# Sheet1.net
KiCad netlist of a schematic drawn in Altium Designer
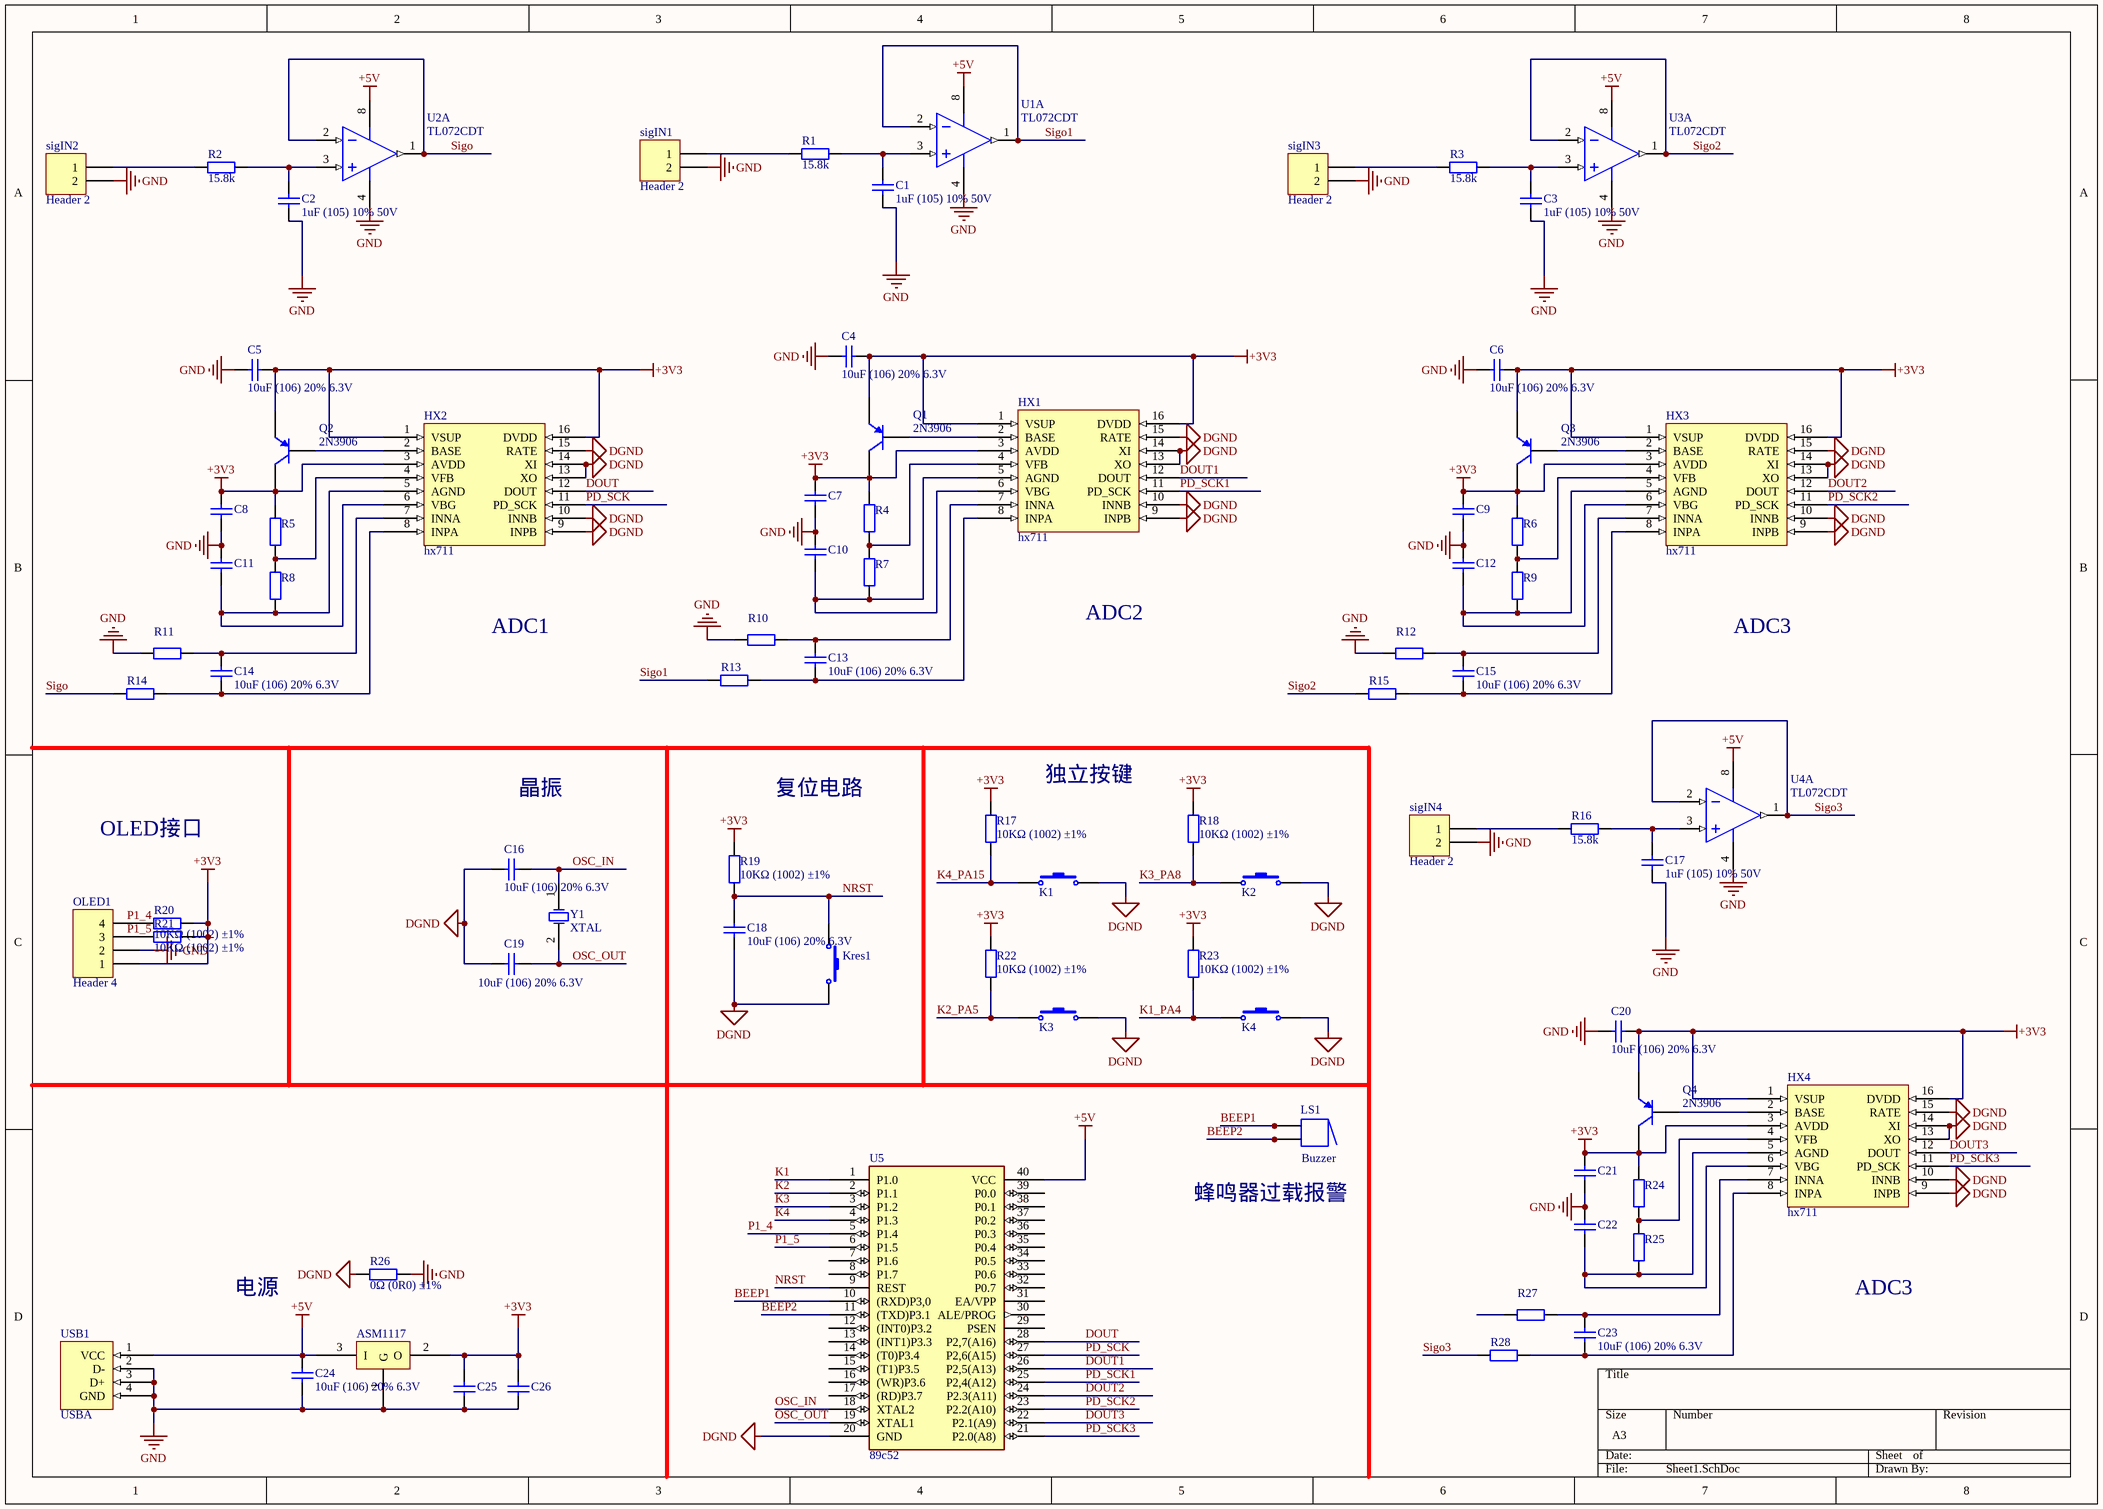
[diagram p0: Sheet1.SchDoc]

(export (version "E")
  (design (tool "Eeschema 10.0.6"))
  (components
    (comp (ref "asm1") (value "ASM1117") (footprint "1117PCB") (libsource (lib "AD603") (part "1117")))
    (comp (ref "C1")
      (value "1uF (105) 10% 50V")
      (footprint "0805_C")
      (description "贴片电容")
      (libsource (lib "Miscellaneous Devices LC") (part "0805 1uF (105) 10% 50V"))
    )
    (comp (ref "C2")
      (value "1uF (105) 10% 50V")
      (footprint "0805_C")
      (description "贴片电容")
      (libsource (lib "Miscellaneous Devices LC") (part "0805 1uF (105) 10% 50V"))
    )
    (comp (ref "C3")
      (value "1uF (105) 10% 50V")
      (footprint "0805_C")
      (description "贴片电容")
      (libsource (lib "Miscellaneous Devices LC") (part "0805 1uF (105) 10% 50V"))
    )
    (comp (ref "C4")
      (value "10uF (106) 20% 6.3V")
      (footprint "0402_C")
      (description "贴片电容")
      (libsource (lib "Miscellaneous Devices LC") (part "0402 10uF (106) 20% 6.3V"))
    )
    (comp (ref "C5")
      (value "10uF (106) 20% 6.3V")
      (footprint "0402_C")
      (description "贴片电容")
      (libsource (lib "Miscellaneous Devices LC") (part "0402 10uF (106) 20% 6.3V"))
    )
    (comp (ref "C6")
      (value "10uF (106) 20% 6.3V")
      (footprint "0402_C")
      (description "贴片电容")
      (libsource (lib "Miscellaneous Devices LC") (part "0402 10uF (106) 20% 6.3V"))
    )
    (comp (ref "C7")
      (value "10uF (106) 20% 6.3V")
      (footprint "0402_C")
      (description "贴片电容")
      (libsource (lib "Miscellaneous Devices LC") (part "0402 10uF (106) 20% 6.3V"))
    )
    (comp (ref "C8")
      (value "10uF (106) 20% 6.3V")
      (footprint "0402_C")
      (description "贴片电容")
      (libsource (lib "Miscellaneous Devices LC") (part "0402 10uF (106) 20% 6.3V"))
    )
    (comp (ref "C9")
      (value "10uF (106) 20% 6.3V")
      (footprint "0402_C")
      (description "贴片电容")
      (libsource (lib "Miscellaneous Devices LC") (part "0402 10uF (106) 20% 6.3V"))
    )
    (comp (ref "C10")
      (value "10uF (106) 20% 6.3V")
      (footprint "0402_C")
      (description "贴片电容")
      (libsource (lib "Miscellaneous Devices LC") (part "0402 10uF (106) 20% 6.3V"))
    )
    (comp (ref "C11")
      (value "10uF (106) 20% 6.3V")
      (footprint "0402_C")
      (description "贴片电容")
      (libsource (lib "Miscellaneous Devices LC") (part "0402 10uF (106) 20% 6.3V"))
    )
    (comp (ref "C12")
      (value "10uF (106) 20% 6.3V")
      (footprint "0402_C")
      (description "贴片电容")
      (libsource (lib "Miscellaneous Devices LC") (part "0402 10uF (106) 20% 6.3V"))
    )
    (comp (ref "C13")
      (value "10uF (106) 20% 6.3V")
      (footprint "0402_C")
      (description "贴片电容")
      (libsource (lib "Miscellaneous Devices LC") (part "0402 10uF (106) 20% 6.3V"))
    )
    (comp (ref "C14")
      (value "10uF (106) 20% 6.3V")
      (footprint "0402_C")
      (description "贴片电容")
      (libsource (lib "Miscellaneous Devices LC") (part "0402 10uF (106) 20% 6.3V"))
    )
    (comp (ref "C15")
      (value "10uF (106) 20% 6.3V")
      (footprint "0402_C")
      (description "贴片电容")
      (libsource (lib "Miscellaneous Devices LC") (part "0402 10uF (106) 20% 6.3V"))
    )
    (comp (ref "C16")
      (value "10uF (106) 20% 6.3V")
      (footprint "0402_C")
      (description "贴片电容")
      (libsource (lib "Miscellaneous Devices LC") (part "0402 10uF (106) 20% 6.3V"))
    )
    (comp (ref "C17")
      (value "1uF (105) 10% 50V")
      (footprint "0805_C")
      (description "贴片电容")
      (libsource (lib "Miscellaneous Devices LC") (part "0805 1uF (105) 10% 50V"))
    )
    (comp (ref "C18")
      (value "10uF (106) 20% 6.3V")
      (footprint "0402_C")
      (description "贴片电容")
      (libsource (lib "Miscellaneous Devices LC") (part "0402 10uF (106) 20% 6.3V"))
    )
    (comp (ref "C19")
      (value "10uF (106) 20% 6.3V")
      (footprint "0402_C")
      (description "贴片电容")
      (libsource (lib "Miscellaneous Devices LC") (part "0402 10uF (106) 20% 6.3V"))
    )
    (comp (ref "C20")
      (value "10uF (106) 20% 6.3V")
      (footprint "0402_C")
      (description "贴片电容")
      (libsource (lib "Miscellaneous Devices LC") (part "0402 10uF (106) 20% 6.3V"))
    )
    (comp (ref "C21")
      (value "10uF (106) 20% 6.3V")
      (footprint "0402_C")
      (description "贴片电容")
      (libsource (lib "Miscellaneous Devices LC") (part "0402 10uF (106) 20% 6.3V"))
    )
    (comp (ref "C22")
      (value "10uF (106) 20% 6.3V")
      (footprint "0402_C")
      (description "贴片电容")
      (libsource (lib "Miscellaneous Devices LC") (part "0402 10uF (106) 20% 6.3V"))
    )
    (comp (ref "C23")
      (value "10uF (106) 20% 6.3V")
      (footprint "0402_C")
      (description "贴片电容")
      (libsource (lib "Miscellaneous Devices LC") (part "0402 10uF (106) 20% 6.3V"))
    )
    (comp (ref "C24")
      (value "10uF (106) 20% 6.3V")
      (footprint "0402_C")
      (description "贴片电容")
      (libsource (lib "Miscellaneous Devices LC") (part "0402 10uF (106) 20% 6.3V"))
    )
    (comp (ref "C25")
      (value "10uF (106) 20% 6.3V")
      (footprint "0402_C")
      (description "贴片电容")
      (libsource (lib "Miscellaneous Devices LC") (part "0402 10uF (106) 20% 6.3V"))
    )
    (comp (ref "C26")
      (value "10uF (106) 20% 6.3V")
      (footprint "0402_C")
      (description "贴片电容")
      (libsource (lib "Miscellaneous Devices LC") (part "0402 10uF (106) 20% 6.3V"))
    )
    (comp (ref "HX1") (value "hx711") (footprint "HX711") (libsource (lib "Schlib1") (part "hx711")))
    (comp (ref "HX2") (value "hx711") (footprint "HX711") (libsource (lib "Schlib1") (part "hx711")))
    (comp (ref "HX3") (value "hx711") (footprint "HX711") (libsource (lib "Schlib1") (part "hx711")))
    (comp (ref "HX4") (value "hx711") (footprint "HX711") (libsource (lib "Schlib1") (part "hx711")))
    (comp (ref "K1") (value "key") (footprint "KEYPCB") (libsource (lib "zhj's footprint") (part "key")))
    (comp (ref "K2") (value "key") (footprint "KEYPCB") (libsource (lib "zhj's footprint") (part "key")))
    (comp (ref "K3") (value "key") (footprint "KEYPCB") (libsource (lib "zhj's footprint") (part "key")))
    (comp (ref "K4") (value "key") (footprint "KEYPCB") (libsource (lib "zhj's footprint") (part "key")))
    (comp (ref "Kres1") (value "key") (footprint "KEYPCB") (libsource (lib "zhj's footprint") (part "key")))
    (comp (ref "LS1")
      (value "Buzzer")
      (footprint "ABSM-1574")
      (description "Magnetic Transducer Buzzer")
      (fields (field (name "PUBLISHER") "Altium Limited"))
      (libsource (lib "Miscellaneous Devices") (part "Buzzer"))
    )
    (comp (ref "OLED1")
      (value "Header 4")
      (footprint "HDR1X4")
      (description "Header, 4-Pin")
      (fields (field (name "PUBLISHER") "Altium Limited"))
      (libsource (lib "Miscellaneous Connectors") (part "Header 4"))
    )
    (comp (ref "Q1")
      (value "2N3906")
      (footprint "TO-92A")
      (description "PNP General Purpose Amplifier")
      (fields (field (name "PUBLISHER") "Altium Limited"))
      (libsource (lib "Miscellaneous Devices") (part "2N3906"))
    )
    (comp (ref "Q2")
      (value "2N3906")
      (footprint "TO-92A")
      (description "PNP General Purpose Amplifier")
      (fields (field (name "PUBLISHER") "Altium Limited"))
      (libsource (lib "Miscellaneous Devices") (part "2N3906"))
    )
    (comp (ref "Q3")
      (value "2N3906")
      (footprint "TO-92A")
      (description "PNP General Purpose Amplifier")
      (fields (field (name "PUBLISHER") "Altium Limited"))
      (libsource (lib "Miscellaneous Devices") (part "2N3906"))
    )
    (comp (ref "Q4")
      (value "2N3906")
      (footprint "TO-92A")
      (description "PNP General Purpose Amplifier")
      (fields (field (name "PUBLISHER") "Altium Limited"))
      (libsource (lib "Miscellaneous Devices") (part "2N3906"))
    )
    (comp (ref "R1")
      (value "15.8k")
      (footprint "0805_R")
      (description "贴片电阻")
      (libsource (lib "Miscellaneous Devices LC") (part "0805 330KΩ (3303) 1%"))
    )
    (comp (ref "R2")
      (value "15.8k")
      (footprint "0805_R")
      (description "贴片电阻")
      (libsource (lib "Miscellaneous Devices LC") (part "0805 330KΩ (3303) 1%"))
    )
    (comp (ref "R3")
      (value "15.8k")
      (footprint "0805_R")
      (description "贴片电阻")
      (libsource (lib "Miscellaneous Devices LC") (part "0805 330KΩ (3303) 1%"))
    )
    (comp (ref "R4")
      (value "10KΩ (1002) ±1%")
      (footprint "0603_R")
      (description "贴片电阻")
      (libsource (lib "Miscellaneous Devices LC") (part "0603 10KΩ (1002) 1%"))
    )
    (comp (ref "R5")
      (value "10KΩ (1002) ±1%")
      (footprint "0603_R")
      (description "贴片电阻")
      (libsource (lib "Miscellaneous Devices LC") (part "0603 10KΩ (1002) 1%"))
    )
    (comp (ref "R6")
      (value "10KΩ (1002) ±1%")
      (footprint "0603_R")
      (description "贴片电阻")
      (libsource (lib "Miscellaneous Devices LC") (part "0603 10KΩ (1002) 1%"))
    )
    (comp (ref "R7")
      (value "10KΩ (1002) ±1%")
      (footprint "0603_R")
      (description "贴片电阻")
      (libsource (lib "Miscellaneous Devices LC") (part "0603 10KΩ (1002) 1%"))
    )
    (comp (ref "R8")
      (value "10KΩ (1002) ±1%")
      (footprint "0603_R")
      (description "贴片电阻")
      (libsource (lib "Miscellaneous Devices LC") (part "0603 10KΩ (1002) 1%"))
    )
    (comp (ref "R9")
      (value "10KΩ (1002) ±1%")
      (footprint "0603_R")
      (description "贴片电阻")
      (libsource (lib "Miscellaneous Devices LC") (part "0603 10KΩ (1002) 1%"))
    )
    (comp (ref "R10")
      (value "1KΩ (1002) ±1%")
      (footprint "0603_R")
      (description "贴片电阻")
      (libsource (lib "") (part "0603 10KΩ (1002) 1%_1"))
    )
    (comp (ref "R11")
      (value "1KΩ (1002) ±1%")
      (footprint "0603_R")
      (description "贴片电阻")
      (libsource (lib "") (part "0603 10KΩ (1002) 1%_1"))
    )
    (comp (ref "R12")
      (value "1KΩ (1002) ±1%")
      (footprint "0603_R")
      (description "贴片电阻")
      (libsource (lib "") (part "0603 10KΩ (1002) 1%_1"))
    )
    (comp (ref "R13")
      (value "1KΩ (1002) ±1%")
      (footprint "0603_R")
      (description "贴片电阻")
      (libsource (lib "") (part "0603 10KΩ (1002) 1%_1"))
    )
    (comp (ref "R14")
      (value "1KΩ (1002) ±1%")
      (footprint "0603_R")
      (description "贴片电阻")
      (libsource (lib "") (part "0603 10KΩ (1002) 1%_1"))
    )
    (comp (ref "R15")
      (value "1KΩ (1002) ±1%")
      (footprint "0603_R")
      (description "贴片电阻")
      (libsource (lib "") (part "0603 10KΩ (1002) 1%_1"))
    )
    (comp (ref "R16")
      (value "15.8k")
      (footprint "0805_R")
      (description "贴片电阻")
      (libsource (lib "Miscellaneous Devices LC") (part "0805 330KΩ (3303) 1%"))
    )
    (comp (ref "R17")
      (value "10KΩ (1002) ±1%")
      (footprint "0603_R")
      (description "贴片电阻")
      (libsource (lib "Miscellaneous Devices LC") (part "0603 10KΩ (1002) 1%"))
    )
    (comp (ref "R18")
      (value "10KΩ (1002) ±1%")
      (footprint "0603_R")
      (description "贴片电阻")
      (libsource (lib "Miscellaneous Devices LC") (part "0603 10KΩ (1002) 1%"))
    )
    (comp (ref "R19")
      (value "10KΩ (1002) ±1%")
      (footprint "0603_R")
      (description "贴片电阻")
      (libsource (lib "Miscellaneous Devices LC") (part "0603 10KΩ (1002) 1%"))
    )
    (comp (ref "R20")
      (value "10KΩ (1002) ±1%")
      (footprint "0603_R")
      (description "贴片电阻")
      (libsource (lib "") (part "0603 10KΩ (1002) 1%_1"))
    )
    (comp (ref "R21")
      (value "10KΩ (1002) ±1%")
      (footprint "0603_R")
      (description "贴片电阻")
      (libsource (lib "") (part "0603 10KΩ (1002) 1%_1"))
    )
    (comp (ref "R22")
      (value "10KΩ (1002) ±1%")
      (footprint "0603_R")
      (description "贴片电阻")
      (libsource (lib "Miscellaneous Devices LC") (part "0603 10KΩ (1002) 1%"))
    )
    (comp (ref "R23")
      (value "10KΩ (1002) ±1%")
      (footprint "0603_R")
      (description "贴片电阻")
      (libsource (lib "Miscellaneous Devices LC") (part "0603 10KΩ (1002) 1%"))
    )
    (comp (ref "R24")
      (value "10KΩ (1002) ±1%")
      (footprint "0603_R")
      (description "贴片电阻")
      (libsource (lib "Miscellaneous Devices LC") (part "0603 10KΩ (1002) 1%"))
    )
    (comp (ref "R25")
      (value "10KΩ (1002) ±1%")
      (footprint "0603_R")
      (description "贴片电阻")
      (libsource (lib "Miscellaneous Devices LC") (part "0603 10KΩ (1002) 1%"))
    )
    (comp (ref "R26")
      (value "0Ω (0R0) ±1%")
      (footprint "0603_R")
      (description "贴片电阻")
      (libsource (lib "Miscellaneous Devices LC") (part "0603 0Ω (0R0) 1%"))
    )
    (comp (ref "R27")
      (value "1KΩ (1002) ±1%")
      (footprint "0603_R")
      (description "贴片电阻")
      (libsource (lib "") (part "0603 10KΩ (1002) 1%_1"))
    )
    (comp (ref "R28")
      (value "1KΩ (1002) ±1%")
      (footprint "0603_R")
      (description "贴片电阻")
      (libsource (lib "") (part "0603 10KΩ (1002) 1%_1"))
    )
    (comp (ref "sigIN1")
      (value "Header 2")
      (footprint "HDR1X2")
      (description "Header, 2-Pin")
      (fields (field (name "PUBLISHER") "Altium Limited"))
      (libsource (lib "Miscellaneous Connectors") (part "Header 2"))
    )
    (comp (ref "sigIN2")
      (value "Header 2")
      (footprint "HDR1X2")
      (description "Header, 2-Pin")
      (fields (field (name "PUBLISHER") "Altium Limited"))
      (libsource (lib "Miscellaneous Connectors") (part "Header 2"))
    )
    (comp (ref "sigIN3")
      (value "Header 2")
      (footprint "HDR1X2")
      (description "Header, 2-Pin")
      (fields (field (name "PUBLISHER") "Altium Limited"))
      (libsource (lib "Miscellaneous Connectors") (part "Header 2"))
    )
    (comp (ref "sigIN4")
      (value "Header 2")
      (footprint "HDR1X2")
      (description "Header, 2-Pin")
      (fields (field (name "PUBLISHER") "Altium Limited"))
      (libsource (lib "Miscellaneous Connectors") (part "Header 2"))
    )
    (comp (ref "U1")
      (value "TL072CDT")
      (footprint "SOIC-8_150mil")
      (description "运放")
      (libsource (lib "Miscellaneous Devices LC") (part "TL072CDT_[C6961]"))
    )
    (comp (ref "U2")
      (value "TL072CDT")
      (footprint "SOIC-8_150mil")
      (description "运放")
      (libsource (lib "Miscellaneous Devices LC") (part "TL072CDT_[C6961]"))
    )
    (comp (ref "U3")
      (value "TL072CDT")
      (footprint "SOIC-8_150mil")
      (description "运放")
      (libsource (lib "Miscellaneous Devices LC") (part "TL072CDT_[C6961]"))
    )
    (comp (ref "U4")
      (value "TL072CDT")
      (footprint "SOIC-8_150mil")
      (description "运放")
      (libsource (lib "Miscellaneous Devices LC") (part "TL072CDT_[C6961]"))
    )
    (comp (ref "U5")
      (value "89c52")
      (footprint "DIP40")
      (description "AT89C52")
      (libsource (lib "HGH") (part "89c52"))
    )
    (comp (ref "USB1") (value "USBA") (footprint "USB-A") (libsource (lib "Schlib2") (part "USBA")))
    (comp (ref "Y1")
      (value "XTAL")
      (footprint "R38")
      (description "Crystal Oscillator")
      (fields (field (name "PUBLISHER") "Altium Limited"))
      (libsource (lib "Miscellaneous Devices") (part "XTAL"))
    )
  )
  (nets
    (net (code "1") (name "+3V3") (class "Default")
      (node (ref "C20") (pin "2") (pinfunction "2_2") (pintype "passive"))
      (node (ref "C21") (pin "1") (pinfunction "1_1") (pintype "passive"))
      (node (ref "C25") (pin "1") (pinfunction "1_1") (pintype "passive"))
      (node (ref "C26") (pin "1") (pinfunction "1_1") (pintype "passive"))
      (node (ref "C4") (pin "2") (pinfunction "2_2") (pintype "passive"))
      (node (ref "C5") (pin "2") (pinfunction "2_2") (pintype "passive"))
      (node (ref "C6") (pin "2") (pinfunction "2_2") (pintype "passive"))
      (node (ref "C7") (pin "1") (pinfunction "1_1") (pintype "passive"))
      (node (ref "C8") (pin "1") (pinfunction "1_1") (pintype "passive"))
      (node (ref "C9") (pin "1") (pinfunction "1_1") (pintype "passive"))
      (node (ref "HX1") (pin "1") (pinfunction "VSUP_1") (pintype "input"))
      (node (ref "HX1") (pin "16") (pinfunction "DVDD_16") (pintype "input"))
      (node (ref "HX1") (pin "3") (pinfunction "AVDD_3") (pintype "input"))
      (node (ref "HX2") (pin "1") (pinfunction "VSUP_1") (pintype "input"))
      (node (ref "HX2") (pin "16") (pinfunction "DVDD_16") (pintype "input"))
      (node (ref "HX2") (pin "3") (pinfunction "AVDD_3") (pintype "input"))
      (node (ref "HX3") (pin "1") (pinfunction "VSUP_1") (pintype "input"))
      (node (ref "HX3") (pin "16") (pinfunction "DVDD_16") (pintype "input"))
      (node (ref "HX3") (pin "3") (pinfunction "AVDD_3") (pintype "input"))
      (node (ref "HX4") (pin "1") (pinfunction "VSUP_1") (pintype "input"))
      (node (ref "HX4") (pin "16") (pinfunction "DVDD_16") (pintype "input"))
      (node (ref "HX4") (pin "3") (pinfunction "AVDD_3") (pintype "input"))
      (node (ref "OLED1") (pin "1") (pinfunction "1_1") (pintype "passive"))
      (node (ref "Q1") (pin "1") (pinfunction "E_1") (pintype "passive"))
      (node (ref "Q1") (pin "3") (pinfunction "C_3") (pintype "passive"))
      (node (ref "Q2") (pin "1") (pinfunction "E_1") (pintype "passive"))
      (node (ref "Q2") (pin "3") (pinfunction "C_3") (pintype "passive"))
      (node (ref "Q3") (pin "1") (pinfunction "E_1") (pintype "passive"))
      (node (ref "Q3") (pin "3") (pinfunction "C_3") (pintype "passive"))
      (node (ref "Q4") (pin "1") (pinfunction "E_1") (pintype "passive"))
      (node (ref "Q4") (pin "3") (pinfunction "C_3") (pintype "passive"))
      (node (ref "R17") (pin "2") (pinfunction "2_2") (pintype "passive"))
      (node (ref "R18") (pin "2") (pinfunction "2_2") (pintype "passive"))
      (node (ref "R19") (pin "2") (pinfunction "2_2") (pintype "passive"))
      (node (ref "R20") (pin "1") (pinfunction "1_1") (pintype "passive"))
      (node (ref "R21") (pin "1") (pinfunction "1_1") (pintype "passive"))
      (node (ref "R22") (pin "2") (pinfunction "2_2") (pintype "passive"))
      (node (ref "R23") (pin "2") (pinfunction "2_2") (pintype "passive"))
      (node (ref "R24") (pin "2") (pinfunction "2_2") (pintype "passive"))
      (node (ref "R4") (pin "2") (pinfunction "2_2") (pintype "passive"))
      (node (ref "R5") (pin "2") (pinfunction "2_2") (pintype "passive"))
      (node (ref "R6") (pin "2") (pinfunction "2_2") (pintype "passive"))
      (node (ref "asm1") (pin "2") (pinfunction "O_2") (pintype "passive"))
    )
    (net (code "2") (name "+5V") (class "Default")
      (node (ref "C24") (pin "1") (pinfunction "1_1") (pintype "passive"))
      (node (ref "U1") (pin "8") (pinfunction "V+_8") (pintype "power_in"))
      (node (ref "U2") (pin "8") (pinfunction "V+_8") (pintype "power_in"))
      (node (ref "U3") (pin "8") (pinfunction "V+_8") (pintype "power_in"))
      (node (ref "U4") (pin "8") (pinfunction "V+_8") (pintype "power_in"))
      (node (ref "U5") (pin "40") (pinfunction "VCC_40") (pintype "power_in"))
      (node (ref "USB1") (pin "1") (pinfunction "VCC_1") (pintype "input"))
      (node (ref "asm1") (pin "3") (pinfunction "I_3") (pintype "passive"))
    )
    (net (code "3") (name "/BEEP1") (class "Default")
      (node (ref "LS1") (pin "1") (pinfunction "1_1") (pintype "passive"))
      (node (ref "LS1") (pin "1A") (pinfunction "1A_1A") (pintype "passive"))
      (node (ref "U5") (pin "10") (pinfunction "(RXD)P3,0_10") (pintype "bidirectional"))
    )
    (net (code "4") (name "/BEEP2") (class "Default")
      (node (ref "LS1") (pin "2") (pinfunction "2_2") (pintype "passive"))
      (node (ref "LS1") (pin "2A") (pinfunction "2A_2A") (pintype "passive"))
      (node (ref "U5") (pin "11") (pinfunction "(TXD)P3.1_11") (pintype "bidirectional"))
    )
    (net (code "5") (name "/DOUT") (class "Default")
      (node (ref "HX2") (pin "12") (pinfunction "DOUT_12") (pintype "input"))
      (node (ref "U5") (pin "28") (pinfunction "P2,7(A16)_28") (pintype "bidirectional"))
    )
    (net (code "6") (name "/DOUT1") (class "Default")
      (node (ref "HX1") (pin "12") (pinfunction "DOUT_12") (pintype "input"))
      (node (ref "U5") (pin "26") (pinfunction "P2,5(A13)_26") (pintype "bidirectional"))
    )
    (net (code "7") (name "/DOUT2") (class "Default")
      (node (ref "HX3") (pin "12") (pinfunction "DOUT_12") (pintype "input"))
      (node (ref "U5") (pin "24") (pinfunction "P2.3(A11)_24") (pintype "bidirectional"))
    )
    (net (code "8") (name "/DOUT3") (class "Default")
      (node (ref "HX4") (pin "12") (pinfunction "DOUT_12") (pintype "input"))
      (node (ref "U5") (pin "22") (pinfunction "P2.1(A9)_22") (pintype "bidirectional"))
    )
    (net (code "9") (name "/K1") (class "Default")
      (node (ref "U5") (pin "1") (pinfunction "P1.0_1") (pintype "passive"))
    )
    (net (code "10") (name "/K1_PA4") (class "Default")
      (node (ref "K4") (pin "1") (pinfunction "1_1") (pintype "passive"))
      (node (ref "R23") (pin "1") (pinfunction "1_1") (pintype "passive"))
    )
    (net (code "11") (name "/K2") (class "Default")
      (node (ref "U5") (pin "2") (pinfunction "P1.1_2") (pintype "bidirectional"))
    )
    (net (code "12") (name "/K2_PA5") (class "Default")
      (node (ref "K3") (pin "1") (pinfunction "1_1") (pintype "passive"))
      (node (ref "R22") (pin "1") (pinfunction "1_1") (pintype "passive"))
    )
    (net (code "13") (name "/K3") (class "Default")
      (node (ref "U5") (pin "3") (pinfunction "P1.2_3") (pintype "bidirectional"))
    )
    (net (code "14") (name "/K3_PA8") (class "Default")
      (node (ref "K2") (pin "1") (pinfunction "1_1") (pintype "passive"))
      (node (ref "R18") (pin "1") (pinfunction "1_1") (pintype "passive"))
    )
    (net (code "15") (name "/K4") (class "Default")
      (node (ref "U5") (pin "4") (pinfunction "P1.3_4") (pintype "bidirectional"))
    )
    (net (code "16") (name "/K4_PA15") (class "Default")
      (node (ref "K1") (pin "1") (pinfunction "1_1") (pintype "passive"))
      (node (ref "R17") (pin "1") (pinfunction "1_1") (pintype "passive"))
    )
    (net (code "17") (name "/NRST") (class "Default")
      (node (ref "C18") (pin "2") (pinfunction "2_2") (pintype "passive"))
      (node (ref "Kres1") (pin "1") (pinfunction "1_1") (pintype "passive"))
      (node (ref "R19") (pin "1") (pinfunction "1_1") (pintype "passive"))
      (node (ref "U5") (pin "9") (pinfunction "REST_9") (pintype "passive"))
    )
    (net (code "18") (name "/OSC_IN") (class "Default")
      (node (ref "C16") (pin "1") (pinfunction "1_1") (pintype "passive"))
      (node (ref "U5") (pin "18") (pinfunction "XTAL2_18") (pintype "bidirectional"))
      (node (ref "Y1") (pin "1") (pinfunction "OSC1_1") (pintype "passive"))
    )
    (net (code "19") (name "/OSC_OUT") (class "Default")
      (node (ref "C19") (pin "1") (pinfunction "1_1") (pintype "passive"))
      (node (ref "U5") (pin "19") (pinfunction "XTAL1_19") (pintype "bidirectional"))
      (node (ref "Y1") (pin "2") (pinfunction "OSC2_2") (pintype "passive"))
    )
    (net (code "20") (name "/P1_4") (class "Default")
      (node (ref "U5") (pin "5") (pinfunction "P1.4_5") (pintype "bidirectional"))
    )
    (net (code "21") (name "/P1_5") (class "Default")
      (node (ref "U5") (pin "6") (pinfunction "P1.5_6") (pintype "bidirectional"))
    )
    (net (code "22") (name "/PD_SCK") (class "Default")
      (node (ref "HX2") (pin "11") (pinfunction "PD_SCK_11") (pintype "input"))
      (node (ref "U5") (pin "27") (pinfunction "P2,6(A15)_27") (pintype "bidirectional"))
    )
    (net (code "23") (name "/PD_SCK1") (class "Default")
      (node (ref "HX1") (pin "11") (pinfunction "PD_SCK_11") (pintype "input"))
      (node (ref "U5") (pin "25") (pinfunction "P2,4(A12)_25") (pintype "bidirectional"))
    )
    (net (code "24") (name "/PD_SCK2") (class "Default")
      (node (ref "HX3") (pin "11") (pinfunction "PD_SCK_11") (pintype "input"))
      (node (ref "U5") (pin "23") (pinfunction "P2.2(A10)_23") (pintype "bidirectional"))
    )
    (net (code "25") (name "/PD_SCK3") (class "Default")
      (node (ref "HX4") (pin "11") (pinfunction "PD_SCK_11") (pintype "input"))
      (node (ref "U5") (pin "21") (pinfunction "P2.0(A8)_21") (pintype "bidirectional"))
    )
    (net (code "26") (name "/Sigo") (class "Default")
      (node (ref "R14") (pin "2") (pinfunction "2_2") (pintype "passive"))
      (node (ref "U2") (pin "1") (pinfunction "OUT_1") (pintype "output"))
      (node (ref "U2") (pin "2") (pinfunction "IN-_2") (pintype "input"))
    )
    (net (code "27") (name "/Sigo1") (class "Default")
      (node (ref "R13") (pin "2") (pinfunction "2_2") (pintype "passive"))
      (node (ref "U1") (pin "1") (pinfunction "OUT_1") (pintype "output"))
      (node (ref "U1") (pin "2") (pinfunction "IN-_2") (pintype "input"))
    )
    (net (code "28") (name "/Sigo2") (class "Default")
      (node (ref "R15") (pin "2") (pinfunction "2_2") (pintype "passive"))
      (node (ref "U3") (pin "1") (pinfunction "OUT_1") (pintype "output"))
      (node (ref "U3") (pin "2") (pinfunction "IN-_2") (pintype "input"))
    )
    (net (code "29") (name "/Sigo3") (class "Default")
      (node (ref "R28") (pin "2") (pinfunction "2_2") (pintype "passive"))
      (node (ref "U4") (pin "1") (pinfunction "OUT_1") (pintype "output"))
      (node (ref "U4") (pin "2") (pinfunction "IN-_2") (pintype "input"))
    )
    (net (code "30") (name "DGND") (class "Default")
      (node (ref "C16") (pin "2") (pinfunction "2_2") (pintype "passive"))
      (node (ref "C18") (pin "1") (pinfunction "1_1") (pintype "passive"))
      (node (ref "C19") (pin "2") (pinfunction "2_2") (pintype "passive"))
      (node (ref "HX1") (pin "10") (pinfunction "INNB_10") (pintype "input"))
      (node (ref "HX1") (pin "13") (pinfunction "XO_13") (pintype "input"))
      (node (ref "HX1") (pin "14") (pinfunction "XI_14") (pintype "input"))
      (node (ref "HX1") (pin "15") (pinfunction "RATE_15") (pintype "input"))
      (node (ref "HX1") (pin "9") (pinfunction "INPB_9") (pintype "input"))
      (node (ref "HX2") (pin "10") (pinfunction "INNB_10") (pintype "input"))
      (node (ref "HX2") (pin "13") (pinfunction "XO_13") (pintype "input"))
      (node (ref "HX2") (pin "14") (pinfunction "XI_14") (pintype "input"))
      (node (ref "HX2") (pin "15") (pinfunction "RATE_15") (pintype "input"))
      (node (ref "HX2") (pin "9") (pinfunction "INPB_9") (pintype "input"))
      (node (ref "HX3") (pin "10") (pinfunction "INNB_10") (pintype "input"))
      (node (ref "HX3") (pin "13") (pinfunction "XO_13") (pintype "input"))
      (node (ref "HX3") (pin "14") (pinfunction "XI_14") (pintype "input"))
      (node (ref "HX3") (pin "15") (pinfunction "RATE_15") (pintype "input"))
      (node (ref "HX3") (pin "9") (pinfunction "INPB_9") (pintype "input"))
      (node (ref "HX4") (pin "10") (pinfunction "INNB_10") (pintype "input"))
      (node (ref "HX4") (pin "13") (pinfunction "XO_13") (pintype "input"))
      (node (ref "HX4") (pin "14") (pinfunction "XI_14") (pintype "input"))
      (node (ref "HX4") (pin "15") (pinfunction "RATE_15") (pintype "input"))
      (node (ref "HX4") (pin "9") (pinfunction "INPB_9") (pintype "input"))
      (node (ref "K1") (pin "2") (pinfunction "2_2") (pintype "passive"))
      (node (ref "K2") (pin "2") (pinfunction "2_2") (pintype "passive"))
      (node (ref "K3") (pin "2") (pinfunction "2_2") (pintype "passive"))
      (node (ref "K4") (pin "2") (pinfunction "2_2") (pintype "passive"))
      (node (ref "Kres1") (pin "2") (pinfunction "2_2") (pintype "passive"))
      (node (ref "R26") (pin "1") (pinfunction "1_1") (pintype "passive"))
      (node (ref "U5") (pin "20") (pinfunction "GND_20") (pintype "power_in"))
    )
    (net (code "31") (name "GND") (class "Default")
      (node (ref "C1") (pin "1") (pinfunction "1_1") (pintype "passive"))
      (node (ref "C10") (pin "1") (pinfunction "1_1") (pintype "passive"))
      (node (ref "C11") (pin "1") (pinfunction "1_1") (pintype "passive"))
      (node (ref "C12") (pin "1") (pinfunction "1_1") (pintype "passive"))
      (node (ref "C17") (pin "1") (pinfunction "1_1") (pintype "passive"))
      (node (ref "C2") (pin "1") (pinfunction "1_1") (pintype "passive"))
      (node (ref "C20") (pin "1") (pinfunction "1_1") (pintype "passive"))
      (node (ref "C21") (pin "2") (pinfunction "2_2") (pintype "passive"))
      (node (ref "C22") (pin "1") (pinfunction "1_1") (pintype "passive"))
      (node (ref "C24") (pin "2") (pinfunction "2_2") (pintype "passive"))
      (node (ref "C25") (pin "2") (pinfunction "2_2") (pintype "passive"))
      (node (ref "C26") (pin "2") (pinfunction "2_2") (pintype "passive"))
      (node (ref "C3") (pin "1") (pinfunction "1_1") (pintype "passive"))
      (node (ref "C4") (pin "1") (pinfunction "1_1") (pintype "passive"))
      (node (ref "C5") (pin "1") (pinfunction "1_1") (pintype "passive"))
      (node (ref "C6") (pin "1") (pinfunction "1_1") (pintype "passive"))
      (node (ref "C7") (pin "2") (pinfunction "2_2") (pintype "passive"))
      (node (ref "C8") (pin "2") (pinfunction "2_2") (pintype "passive"))
      (node (ref "C9") (pin "2") (pinfunction "2_2") (pintype "passive"))
      (node (ref "OLED1") (pin "2") (pinfunction "2_2") (pintype "passive"))
      (node (ref "R10") (pin "2") (pinfunction "2_2") (pintype "passive"))
      (node (ref "R11") (pin "2") (pinfunction "2_2") (pintype "passive"))
      (node (ref "R12") (pin "2") (pinfunction "2_2") (pintype "passive"))
      (node (ref "R26") (pin "2") (pinfunction "2_2") (pintype "passive"))
      (node (ref "U1") (pin "4") (pinfunction "V-_4") (pintype "power_in"))
      (node (ref "U2") (pin "4") (pinfunction "V-_4") (pintype "power_in"))
      (node (ref "U3") (pin "4") (pinfunction "V-_4") (pintype "power_in"))
      (node (ref "U4") (pin "4") (pinfunction "V-_4") (pintype "power_in"))
      (node (ref "USB1") (pin "2") (pinfunction "D-_2") (pintype "input"))
      (node (ref "USB1") (pin "3") (pinfunction "D+_3") (pintype "input"))
      (node (ref "USB1") (pin "4") (pinfunction "GND_4") (pintype "input"))
      (node (ref "asm1") (pin "1") (pinfunction "G_1") (pintype "passive"))
      (node (ref "sigIN1") (pin "2") (pinfunction "2_2") (pintype "passive"))
      (node (ref "sigIN2") (pin "2") (pinfunction "2_2") (pintype "passive"))
      (node (ref "sigIN3") (pin "2") (pinfunction "2_2") (pintype "passive"))
      (node (ref "sigIN4") (pin "2") (pinfunction "2_2") (pintype "passive"))
    )
    (net (code "32") (name "Net-(HX1-AGND)") (class "Default")
      (node (ref "C10") (pin "2") (pinfunction "2_2") (pintype "passive"))
      (node (ref "HX1") (pin "5") (pinfunction "AGND_5") (pintype "input"))
      (node (ref "HX1") (pin "6") (pinfunction "VBG_6") (pintype "input"))
      (node (ref "R7") (pin "1") (pinfunction "1_1") (pintype "passive"))
    )
    (net (code "33") (name "Net-(HX1-BASE)") (class "Default")
      (node (ref "HX1") (pin "2") (pinfunction "BASE_2") (pintype "input"))
      (node (ref "Q1") (pin "2") (pinfunction "B_2") (pintype "passive"))
    )
    (net (code "34") (name "Net-(HX1-INNA)") (class "Default")
      (node (ref "C13") (pin "1") (pinfunction "1_1") (pintype "passive"))
      (node (ref "HX1") (pin "7") (pinfunction "INNA_7") (pintype "input"))
      (node (ref "R10") (pin "1") (pinfunction "1_1") (pintype "passive"))
    )
    (net (code "35") (name "Net-(HX1-INPA)") (class "Default")
      (node (ref "C13") (pin "2") (pinfunction "2_2") (pintype "passive"))
      (node (ref "HX1") (pin "8") (pinfunction "INPA_8") (pintype "input"))
      (node (ref "R13") (pin "1") (pinfunction "1_1") (pintype "passive"))
    )
    (net (code "36") (name "Net-(HX1-VFB)") (class "Default")
      (node (ref "HX1") (pin "4") (pinfunction "VFB_4") (pintype "input"))
      (node (ref "R4") (pin "1") (pinfunction "1_1") (pintype "passive"))
      (node (ref "R7") (pin "2") (pinfunction "2_2") (pintype "passive"))
    )
    (net (code "37") (name "Net-(HX2-AGND)") (class "Default")
      (node (ref "C11") (pin "2") (pinfunction "2_2") (pintype "passive"))
      (node (ref "HX2") (pin "5") (pinfunction "AGND_5") (pintype "input"))
      (node (ref "HX2") (pin "6") (pinfunction "VBG_6") (pintype "input"))
      (node (ref "R8") (pin "1") (pinfunction "1_1") (pintype "passive"))
    )
    (net (code "38") (name "Net-(HX2-BASE)") (class "Default")
      (node (ref "HX2") (pin "2") (pinfunction "BASE_2") (pintype "input"))
      (node (ref "Q2") (pin "2") (pinfunction "B_2") (pintype "passive"))
    )
    (net (code "39") (name "Net-(HX2-INNA)") (class "Default")
      (node (ref "C14") (pin "1") (pinfunction "1_1") (pintype "passive"))
      (node (ref "HX2") (pin "7") (pinfunction "INNA_7") (pintype "input"))
      (node (ref "R11") (pin "1") (pinfunction "1_1") (pintype "passive"))
    )
    (net (code "40") (name "Net-(HX2-INPA)") (class "Default")
      (node (ref "C14") (pin "2") (pinfunction "2_2") (pintype "passive"))
      (node (ref "HX2") (pin "8") (pinfunction "INPA_8") (pintype "input"))
      (node (ref "R14") (pin "1") (pinfunction "1_1") (pintype "passive"))
    )
    (net (code "41") (name "Net-(HX2-VFB)") (class "Default")
      (node (ref "HX2") (pin "4") (pinfunction "VFB_4") (pintype "input"))
      (node (ref "R5") (pin "1") (pinfunction "1_1") (pintype "passive"))
      (node (ref "R8") (pin "2") (pinfunction "2_2") (pintype "passive"))
    )
    (net (code "42") (name "Net-(HX3-AGND)") (class "Default")
      (node (ref "C12") (pin "2") (pinfunction "2_2") (pintype "passive"))
      (node (ref "HX3") (pin "5") (pinfunction "AGND_5") (pintype "input"))
      (node (ref "HX3") (pin "6") (pinfunction "VBG_6") (pintype "input"))
      (node (ref "R9") (pin "1") (pinfunction "1_1") (pintype "passive"))
    )
    (net (code "43") (name "Net-(HX3-BASE)") (class "Default")
      (node (ref "HX3") (pin "2") (pinfunction "BASE_2") (pintype "input"))
      (node (ref "Q3") (pin "2") (pinfunction "B_2") (pintype "passive"))
    )
    (net (code "44") (name "Net-(HX3-INNA)") (class "Default")
      (node (ref "C15") (pin "1") (pinfunction "1_1") (pintype "passive"))
      (node (ref "HX3") (pin "7") (pinfunction "INNA_7") (pintype "input"))
      (node (ref "R12") (pin "1") (pinfunction "1_1") (pintype "passive"))
    )
    (net (code "45") (name "Net-(HX3-INPA)") (class "Default")
      (node (ref "C15") (pin "2") (pinfunction "2_2") (pintype "passive"))
      (node (ref "HX3") (pin "8") (pinfunction "INPA_8") (pintype "input"))
      (node (ref "R15") (pin "1") (pinfunction "1_1") (pintype "passive"))
    )
    (net (code "46") (name "Net-(HX3-VFB)") (class "Default")
      (node (ref "HX3") (pin "4") (pinfunction "VFB_4") (pintype "input"))
      (node (ref "R6") (pin "1") (pinfunction "1_1") (pintype "passive"))
      (node (ref "R9") (pin "2") (pinfunction "2_2") (pintype "passive"))
    )
    (net (code "47") (name "Net-(HX4-AGND)") (class "Default")
      (node (ref "C22") (pin "2") (pinfunction "2_2") (pintype "passive"))
      (node (ref "HX4") (pin "5") (pinfunction "AGND_5") (pintype "input"))
      (node (ref "HX4") (pin "6") (pinfunction "VBG_6") (pintype "input"))
      (node (ref "R25") (pin "1") (pinfunction "1_1") (pintype "passive"))
    )
    (net (code "48") (name "Net-(HX4-BASE)") (class "Default")
      (node (ref "HX4") (pin "2") (pinfunction "BASE_2") (pintype "input"))
      (node (ref "Q4") (pin "2") (pinfunction "B_2") (pintype "passive"))
    )
    (net (code "49") (name "Net-(HX4-INNA)") (class "Default")
      (node (ref "C23") (pin "1") (pinfunction "1_1") (pintype "passive"))
      (node (ref "HX4") (pin "7") (pinfunction "INNA_7") (pintype "input"))
      (node (ref "R27") (pin "1") (pinfunction "1_1") (pintype "passive"))
    )
    (net (code "50") (name "Net-(HX4-INPA)") (class "Default")
      (node (ref "C23") (pin "2") (pinfunction "2_2") (pintype "passive"))
      (node (ref "HX4") (pin "8") (pinfunction "INPA_8") (pintype "input"))
      (node (ref "R28") (pin "1") (pinfunction "1_1") (pintype "passive"))
    )
    (net (code "51") (name "Net-(HX4-VFB)") (class "Default")
      (node (ref "HX4") (pin "4") (pinfunction "VFB_4") (pintype "input"))
      (node (ref "R24") (pin "1") (pinfunction "1_1") (pintype "passive"))
      (node (ref "R25") (pin "2") (pinfunction "2_2") (pintype "passive"))
    )
    (net (code "52") (name "Net-(OLED1-Pad3)") (class "Default")
      (node (ref "OLED1") (pin "3") (pinfunction "3_3") (pintype "passive"))
      (node (ref "R21") (pin "2") (pinfunction "2_2") (pintype "passive"))
    )
    (net (code "53") (name "Net-(OLED1-Pad4)") (class "Default")
      (node (ref "OLED1") (pin "4") (pinfunction "4_4") (pintype "passive"))
      (node (ref "R20") (pin "2") (pinfunction "2_2") (pintype "passive"))
    )
    (net (code "54") (name "Net-(R1-Pad1)") (class "Default")
      (node (ref "R1") (pin "1") (pinfunction "1_1") (pintype "passive"))
      (node (ref "sigIN1") (pin "1") (pinfunction "1_1") (pintype "passive"))
    )
    (net (code "55") (name "Net-(R2-Pad1)") (class "Default")
      (node (ref "R2") (pin "1") (pinfunction "1_1") (pintype "passive"))
      (node (ref "sigIN2") (pin "1") (pinfunction "1_1") (pintype "passive"))
    )
    (net (code "56") (name "Net-(R3-Pad1)") (class "Default")
      (node (ref "R3") (pin "1") (pinfunction "1_1") (pintype "passive"))
      (node (ref "sigIN3") (pin "1") (pinfunction "1_1") (pintype "passive"))
    )
    (net (code "57") (name "Net-(R16-Pad1)") (class "Default")
      (node (ref "R16") (pin "1") (pinfunction "1_1") (pintype "passive"))
      (node (ref "sigIN4") (pin "1") (pinfunction "1_1") (pintype "passive"))
    )
    (net (code "58") (name "Net-(U1A-IN+)") (class "Default")
      (node (ref "C1") (pin "2") (pinfunction "2_2") (pintype "passive"))
      (node (ref "R1") (pin "2") (pinfunction "2_2") (pintype "passive"))
      (node (ref "U1") (pin "3") (pinfunction "IN+_3") (pintype "input"))
    )
    (net (code "59") (name "Net-(U2A-IN+)") (class "Default")
      (node (ref "C2") (pin "2") (pinfunction "2_2") (pintype "passive"))
      (node (ref "R2") (pin "2") (pinfunction "2_2") (pintype "passive"))
      (node (ref "U2") (pin "3") (pinfunction "IN+_3") (pintype "input"))
    )
    (net (code "60") (name "Net-(U3A-IN+)") (class "Default")
      (node (ref "C3") (pin "2") (pinfunction "2_2") (pintype "passive"))
      (node (ref "R3") (pin "2") (pinfunction "2_2") (pintype "passive"))
      (node (ref "U3") (pin "3") (pinfunction "IN+_3") (pintype "input"))
    )
    (net (code "61") (name "Net-(U4A-IN+)") (class "Default")
      (node (ref "C17") (pin "2") (pinfunction "2_2") (pintype "passive"))
      (node (ref "R16") (pin "2") (pinfunction "2_2") (pintype "passive"))
      (node (ref "U4") (pin "3") (pinfunction "IN+_3") (pintype "input"))
    )
    (net (code "62") (name "unconnected-(R27-Pad2)") (class "Default")
      (node (ref "R27") (pin "2") (pinfunction "2_2") (pintype "passive"))
    )
    (net (code "63") (name "unconnected-(U5-(INT0)P3.2-Pad12)") (class "Default")
      (node (ref "U5") (pin "12") (pinfunction "(INT0)P3.2_12") (pintype "bidirectional"))
    )
    (net (code "64") (name "unconnected-(U5-(INT1)P3.3-Pad13)") (class "Default")
      (node (ref "U5") (pin "13") (pinfunction "(INT1)P3.3_13") (pintype "bidirectional"))
    )
    (net (code "65") (name "unconnected-(U5-(RD)P3.7-Pad17)") (class "Default")
      (node (ref "U5") (pin "17") (pinfunction "(RD)P3.7_17") (pintype "bidirectional"))
    )
    (net (code "66") (name "unconnected-(U5-(T0)P3.4-Pad14)") (class "Default")
      (node (ref "U5") (pin "14") (pinfunction "(T0)P3.4_14") (pintype "bidirectional"))
    )
    (net (code "67") (name "unconnected-(U5-(T1)P3.5-Pad15)") (class "Default")
      (node (ref "U5") (pin "15") (pinfunction "(T1)P3.5_15") (pintype "bidirectional"))
    )
    (net (code "68") (name "unconnected-(U5-(WR)P3.6-Pad16)") (class "Default")
      (node (ref "U5") (pin "16") (pinfunction "(WR)P3.6_16") (pintype "bidirectional"))
    )
    (net (code "69") (name "unconnected-(U5-ALE{slash}PROG-Pad30)") (class "Default")
      (node (ref "U5") (pin "30") (pinfunction "ALE/PROG_30") (pintype "output"))
    )
    (net (code "70") (name "unconnected-(U5-EA{slash}VPP-Pad31)") (class "Default")
      (node (ref "U5") (pin "31") (pinfunction "EA/VPP_31") (pintype "power_in"))
    )
    (net (code "71") (name "unconnected-(U5-P0.0-Pad39)") (class "Default")
      (node (ref "U5") (pin "39") (pinfunction "P0.0_39") (pintype "bidirectional"))
    )
    (net (code "72") (name "unconnected-(U5-P0.1-Pad38)") (class "Default")
      (node (ref "U5") (pin "38") (pinfunction "P0.1_38") (pintype "bidirectional"))
    )
    (net (code "73") (name "unconnected-(U5-P0.2-Pad37)") (class "Default")
      (node (ref "U5") (pin "37") (pinfunction "P0.2_37") (pintype "bidirectional"))
    )
    (net (code "74") (name "unconnected-(U5-P0.3-Pad36)") (class "Default")
      (node (ref "U5") (pin "36") (pinfunction "P0.3_36") (pintype "bidirectional"))
    )
    (net (code "75") (name "unconnected-(U5-P0.4-Pad35)") (class "Default")
      (node (ref "U5") (pin "35") (pinfunction "P0.4_35") (pintype "bidirectional"))
    )
    (net (code "76") (name "unconnected-(U5-P0.5-Pad34)") (class "Default")
      (node (ref "U5") (pin "34") (pinfunction "P0.5_34") (pintype "bidirectional"))
    )
    (net (code "77") (name "unconnected-(U5-P0.6-Pad33)") (class "Default")
      (node (ref "U5") (pin "33") (pinfunction "P0.6_33") (pintype "bidirectional"))
    )
    (net (code "78") (name "unconnected-(U5-P0.7-Pad32)") (class "Default")
      (node (ref "U5") (pin "32") (pinfunction "P0.7_32") (pintype "bidirectional"))
    )
    (net (code "79") (name "unconnected-(U5-P1.6-Pad7)") (class "Default")
      (node (ref "U5") (pin "7") (pinfunction "P1.6_7") (pintype "bidirectional"))
    )
    (net (code "80") (name "unconnected-(U5-P1.7-Pad8)") (class "Default")
      (node (ref "U5") (pin "8") (pinfunction "P1.7_8") (pintype "bidirectional"))
    )
    (net (code "81") (name "unconnected-(U5-PSEN-Pad29)") (class "Default")
      (node (ref "U5") (pin "29") (pinfunction "PSEN_29") (pintype "open_emitter"))
    )
  )
)
